# RST_N_Switch.net
KiCad netlist of a schematic drawn in Altium Designer
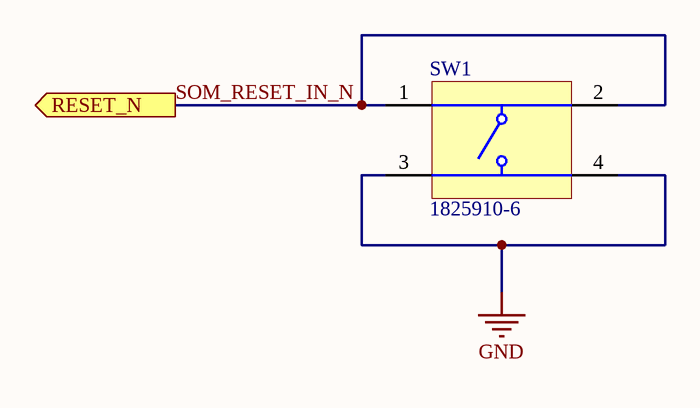
[diagram p0: RST_N_Switch.SchDoc]

(export (version "E")
  (design (tool "Eeschema 10.0.6"))
  (components
    (comp (ref "SW1")
      (value "1825910-6")
      (footprint "TECO-1825910-6_V")
      (description "Tact Switch, SPST-NO, 0.05 A, -35 to 85 degC, 4-Pin THD, RoHS, Bulk")
      (fields (field (name "MANUFACTURER") "TE Connectivity"))
      (libsource (lib "Altium Content Vault") (part "SW-SPST-4_A"))
    )
  )
  (nets
    (net (code "1") (name "/SOM_RESET_IN_N") (class "Default")
      (node (ref "SW1") (pin "1") (pinfunction "1_1") (pintype "passive"))
      (node (ref "SW1") (pin "2") (pinfunction "2_2") (pintype "passive"))
    )
    (net (code "2") (name "GND") (class "Default")
      (node (ref "SW1") (pin "3") (pinfunction "3_3") (pintype "passive"))
      (node (ref "SW1") (pin "4") (pinfunction "4_4") (pintype "passive"))
    )
  )
)
